# ProPrj_MPU6500__2025-10-02.net
KiCad netlist of a schematic drawn in EasyEDA Pro
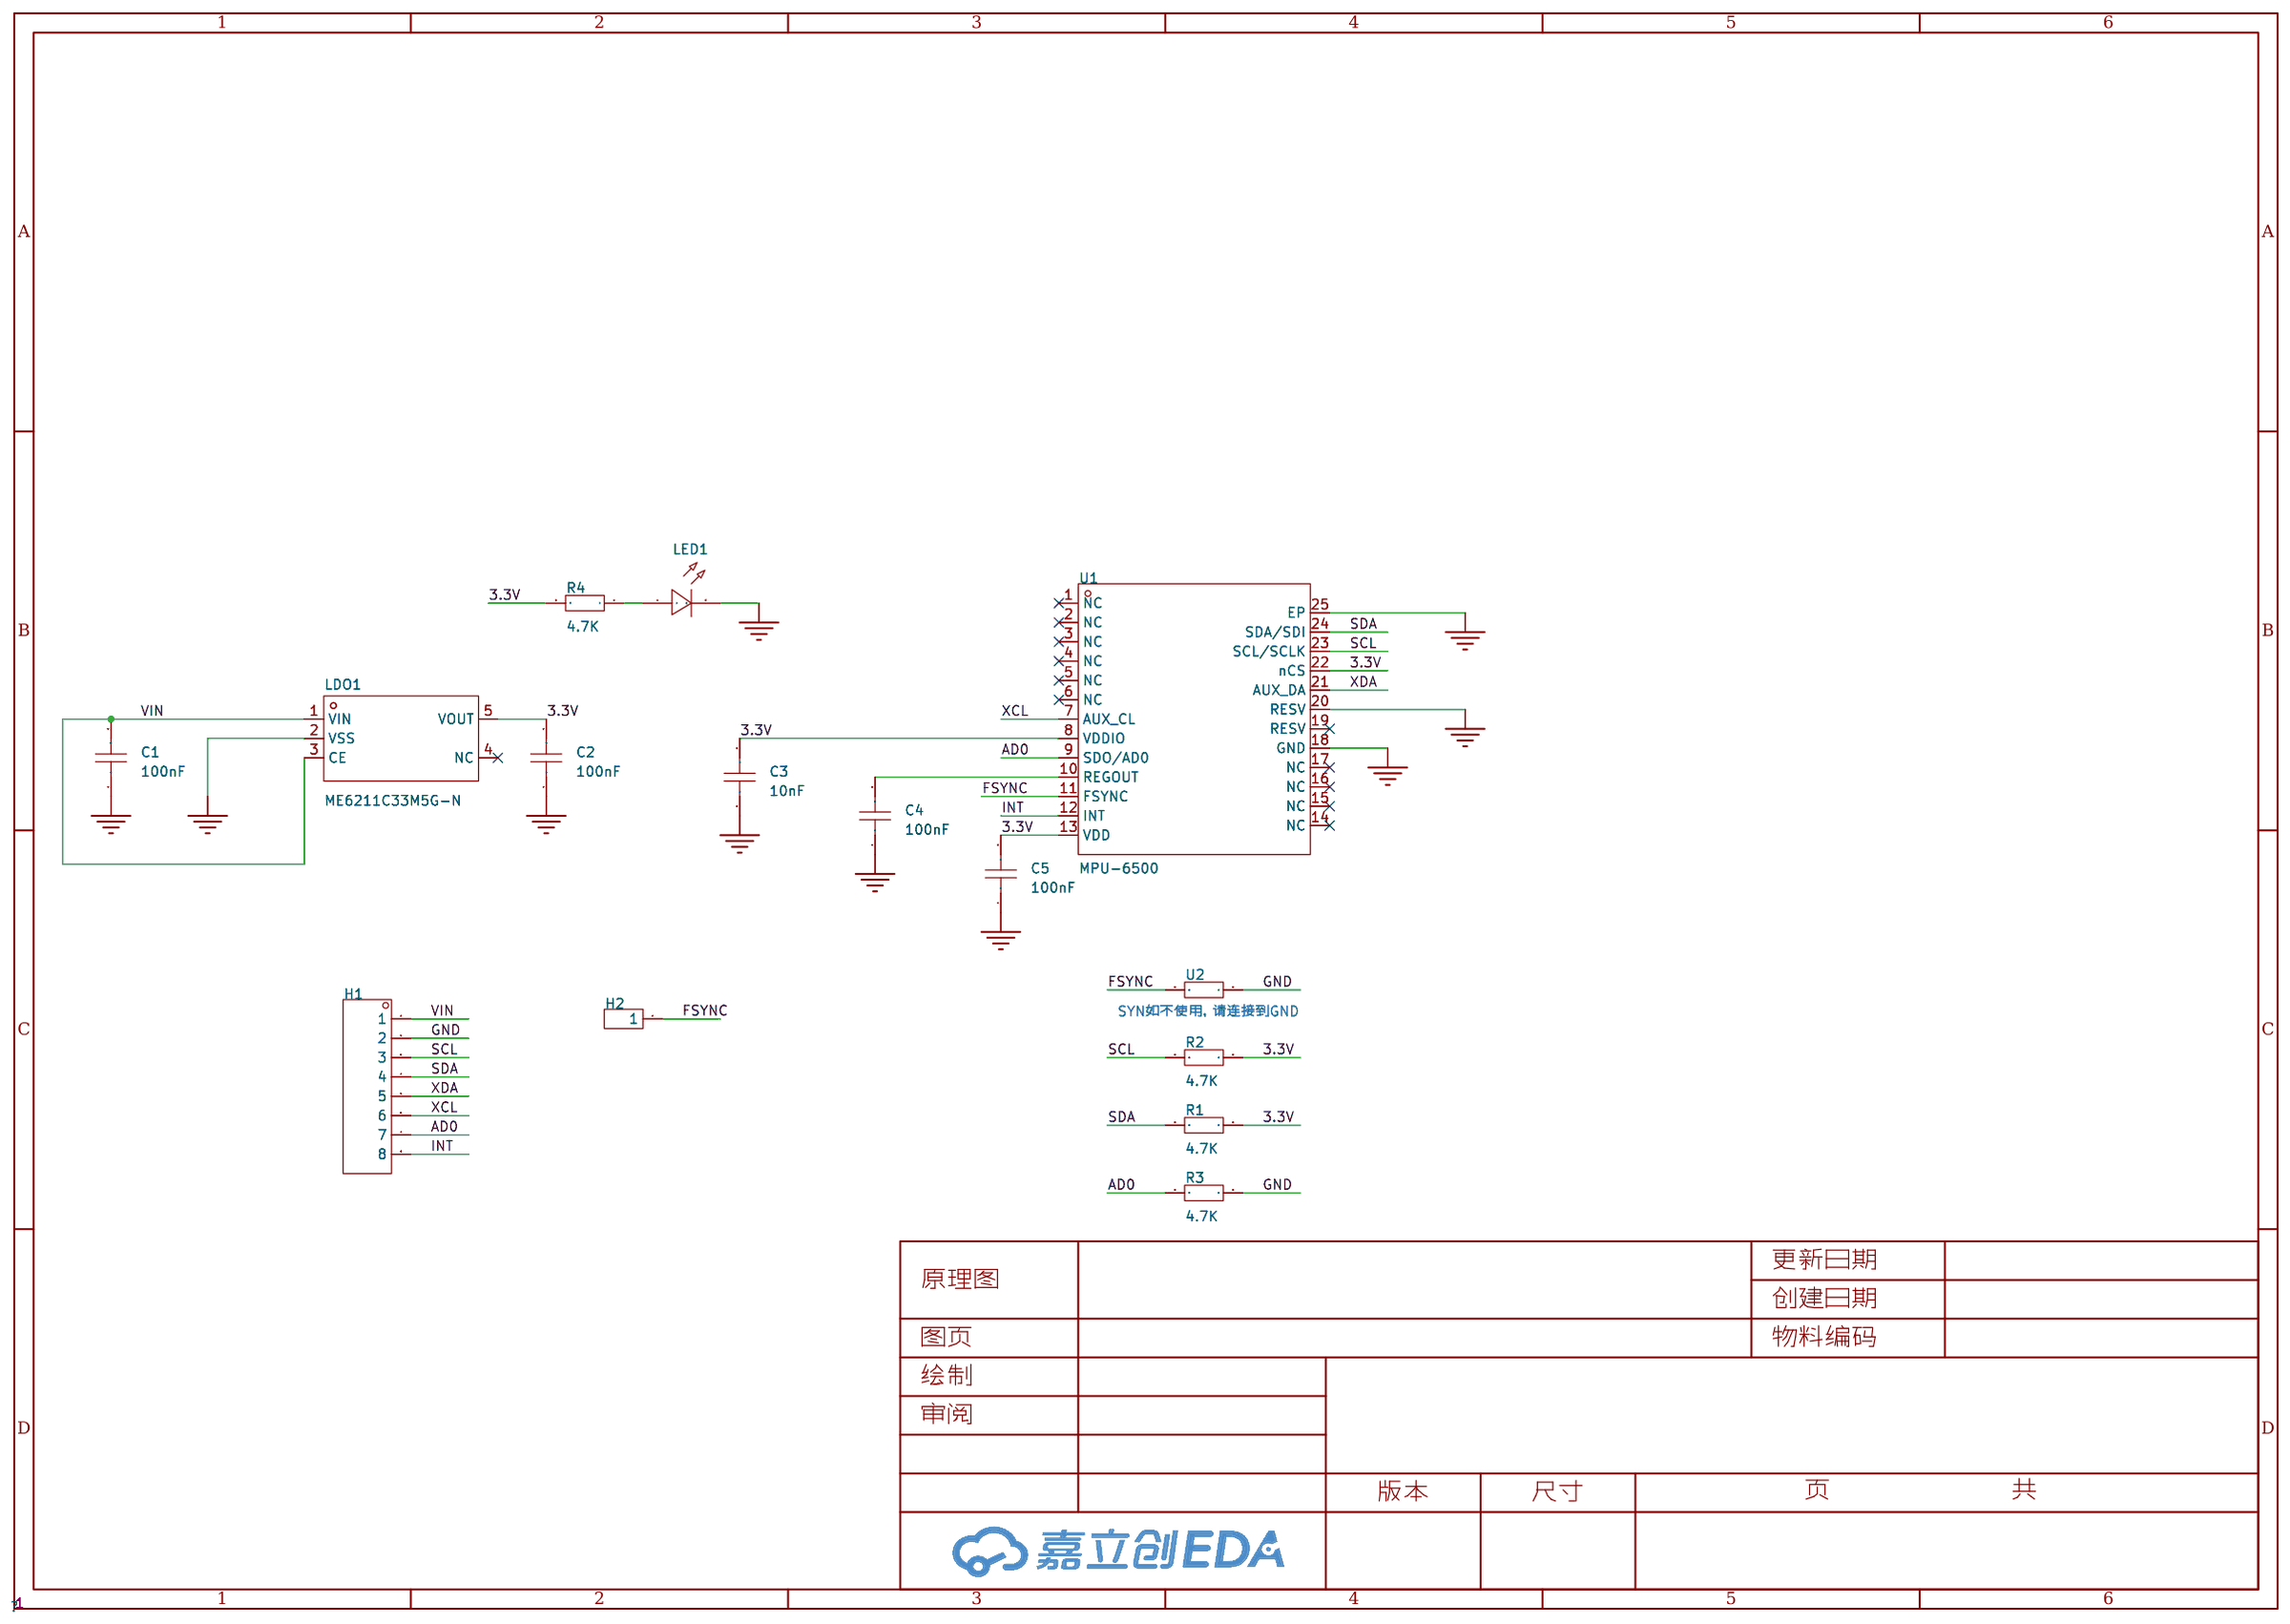
[diagram p0: schematic sheet]

(export (version "E")
  (design (tool "Eeschema 10.0.6"))
  (components
    (comp (ref "C1")
      (value "100nF")
      (footprint "easyedapro:C0603")
      (libsource (lib "easyedapro") (part "CapAcitance"))
    )
    (comp (ref "C2")
      (value "100nF")
      (footprint "easyedapro:C0603")
      (libsource (lib "easyedapro") (part "CapAcitance"))
    )
    (comp (ref "C3")
      (value "10nF")
      (footprint "easyedapro:C0603")
      (libsource (lib "easyedapro") (part "CapAcitance"))
    )
    (comp (ref "C4")
      (value "100nF")
      (footprint "easyedapro:C0603")
      (libsource (lib "easyedapro") (part "CapAcitance"))
    )
    (comp (ref "C5")
      (value "100nF")
      (footprint "easyedapro:C0603")
      (libsource (lib "easyedapro") (part "CapAcitance"))
    )
    (comp (ref "H1")
      (value "~")
      (footprint "easyedapro:HDR-TH_8P-P2.54-V-M")
      (libsource (lib "easyedapro") (part "Header-Male-2.54_1x8"))
    )
    (comp (ref "H2")
      (value "~")
      (footprint "easyedapro:HDR-TH_1P-V-M_XKB_X4611WV-01I-C28D40")
      (libsource (lib "easyedapro") (part "HDR_1x1"))
    )
    (comp (ref "LDO1")
      (value "ME6211C33M5G-N")
      (footprint "easyedapro:SOT-23-5_L3.0-W1.7-P0.95-LS2.8-BL")
      (description "输出类型:固定;最大输入电压:6V;输出电压:3.3V;最大输出电流:500mA;电源纹波抑制比(PSRR):70dB;输出极性:正极;")
      (fields (field (name "Manufacturer") "MICRONE(南京微盟)"))
      (libsource (lib "easyedapro") (part "ME6211C33M5G-N"))
    )
    (comp (ref "LED1")
      (value "~")
      (footprint "easyedapro:LED_0603_RED")
      (libsource (lib "easyedapro") (part "LED0603_R"))
    )
    (comp (ref "R1") (value "4.7K") (footprint "easyedapro:R0603") (libsource (lib "easyedapro") (part "电阻")))
    (comp (ref "R2") (value "4.7K") (footprint "easyedapro:R0603") (libsource (lib "easyedapro") (part "电阻")))
    (comp (ref "R3") (value "4.7K") (footprint "easyedapro:R0603") (libsource (lib "easyedapro") (part "电阻")))
    (comp (ref "R4") (value "4.7K") (footprint "easyedapro:R0603") (libsource (lib "easyedapro") (part "电阻")))
    (comp (ref "U1")
      (value "MPU-6500")
      (footprint "easyedapro:QFN-24_L3.0-W3.0-P0.40-BL-EP")
      (description "传感器类型:加速度计陀螺仪;")
      (fields (field (name "Manufacturer") "TDK InvenSense(应美盛)"))
      (libsource (lib "easyedapro") (part "MPU6500"))
    )
    (comp (ref "U2")
      (value "~")
      (footprint "easyedapro:R0603")
      (description "0603封装的跳线")
      (fields
        (field (name "Manufacturer Part") "0603WAF2200T5E")
        (field (name "Manufacturer") "UNI-ROYAL(厚声)")
      )
      (libsource (lib "easyedapro") (part "0603"))
    )
  )
  (nets
    (net (code "1") (name "/3.3V") (class "Default")
      (node (ref "C2") (pin "2") (pinfunction "2_2") (pintype "input"))
      (node (ref "C3") (pin "2") (pinfunction "2_2") (pintype "input"))
      (node (ref "C5") (pin "2") (pinfunction "2_2") (pintype "input"))
      (node (ref "LDO1") (pin "5") (pinfunction "VOUT_5") (pintype "input"))
      (node (ref "R1") (pin "1") (pinfunction "1_1") (pintype "input"))
      (node (ref "R2") (pin "1") (pinfunction "1_1") (pintype "input"))
      (node (ref "R4") (pin "2") (pinfunction "2_2") (pintype "input"))
      (node (ref "U1") (pin "13") (pinfunction "VDD_13") (pintype "unspecified"))
      (node (ref "U1") (pin "22") (pinfunction "nCS_22") (pintype "unspecified"))
      (node (ref "U1") (pin "8") (pinfunction "VDDIO_8") (pintype "unspecified"))
    )
    (net (code "2") (name "/AD0") (class "Default")
      (node (ref "H1") (pin "7") (pinfunction "7_7") (pintype "unspecified"))
      (node (ref "R3") (pin "2") (pinfunction "2_2") (pintype "input"))
      (node (ref "U1") (pin "9") (pinfunction "SDO/AD0_9") (pintype "unspecified"))
    )
    (net (code "3") (name "/FSYNC") (class "Default")
      (node (ref "H2") (pin "1") (pinfunction "1_1") (pintype "unspecified"))
      (node (ref "U1") (pin "11") (pinfunction "FSYNC_11") (pintype "unspecified"))
      (node (ref "U2") (pin "2") (pinfunction "2_2") (pintype "input"))
    )
    (net (code "4") (name "/INT") (class "Default")
      (node (ref "H1") (pin "8") (pinfunction "8_8") (pintype "unspecified"))
      (node (ref "U1") (pin "12") (pinfunction "INT_12") (pintype "unspecified"))
    )
    (net (code "5") (name "/SCL") (class "Default")
      (node (ref "H1") (pin "3") (pinfunction "3_3") (pintype "unspecified"))
      (node (ref "R2") (pin "2") (pinfunction "2_2") (pintype "input"))
      (node (ref "U1") (pin "23") (pinfunction "SCL/SCLK_23") (pintype "unspecified"))
    )
    (net (code "6") (name "/SDA") (class "Default")
      (node (ref "H1") (pin "4") (pinfunction "4_4") (pintype "unspecified"))
      (node (ref "R1") (pin "2") (pinfunction "2_2") (pintype "input"))
      (node (ref "U1") (pin "24") (pinfunction "SDA/SDI_24") (pintype "unspecified"))
    )
    (net (code "7") (name "/VIN") (class "Default")
      (node (ref "C1") (pin "2") (pinfunction "2_2") (pintype "input"))
      (node (ref "H1") (pin "1") (pinfunction "1_1") (pintype "unspecified"))
      (node (ref "LDO1") (pin "1") (pinfunction "VIN_1") (pintype "input"))
      (node (ref "LDO1") (pin "3") (pinfunction "CE_3") (pintype "input"))
    )
    (net (code "8") (name "/XCL") (class "Default")
      (node (ref "H1") (pin "6") (pinfunction "6_6") (pintype "unspecified"))
      (node (ref "U1") (pin "7") (pinfunction "AUX_CL_7") (pintype "unspecified"))
    )
    (net (code "9") (name "/XDA") (class "Default")
      (node (ref "H1") (pin "5") (pinfunction "5_5") (pintype "unspecified"))
      (node (ref "U1") (pin "21") (pinfunction "AUX_DA_21") (pintype "unspecified"))
    )
    (net (code "10") (name "GND") (class "Default")
      (node (ref "C1") (pin "1") (pinfunction "1_1") (pintype "input"))
      (node (ref "C2") (pin "1") (pinfunction "1_1") (pintype "input"))
      (node (ref "C3") (pin "1") (pinfunction "1_1") (pintype "input"))
      (node (ref "C4") (pin "1") (pinfunction "1_1") (pintype "input"))
      (node (ref "C5") (pin "1") (pinfunction "1_1") (pintype "input"))
      (node (ref "H1") (pin "2") (pinfunction "2_2") (pintype "unspecified"))
      (node (ref "LDO1") (pin "2") (pinfunction "VSS_2") (pintype "input"))
      (node (ref "LED1") (pin "2") (pinfunction "C_2") (pintype "input"))
      (node (ref "R3") (pin "1") (pinfunction "1_1") (pintype "input"))
      (node (ref "U1") (pin "18") (pinfunction "GND_18") (pintype "unspecified"))
      (node (ref "U1") (pin "20") (pinfunction "RESV_20") (pintype "unspecified"))
      (node (ref "U1") (pin "25") (pinfunction "EP_25") (pintype "unspecified"))
      (node (ref "U2") (pin "1") (pinfunction "1_1") (pintype "input"))
    )
    (net (code "11") (name "Net-(LED1-A)") (class "Default")
      (node (ref "LED1") (pin "1") (pinfunction "A_1") (pintype "input"))
      (node (ref "R4") (pin "1") (pinfunction "1_1") (pintype "input"))
    )
    (net (code "12") (name "Net-(U1-REGOUT)") (class "Default")
      (node (ref "C4") (pin "2") (pinfunction "2_2") (pintype "input"))
      (node (ref "U1") (pin "10") (pinfunction "REGOUT_10") (pintype "unspecified"))
    )
    (net (code "13") (name "unconnected-(LDO1-NC-Pad4)") (class "Default")
      (node (ref "LDO1") (pin "4") (pinfunction "NC_4") (pintype "input+no_connect"))
    )
    (net (code "14") (name "unconnected-(U1-NC-Pad1)") (class "Default")
      (node (ref "U1") (pin "1") (pinfunction "NC_1") (pintype "unspecified+no_connect"))
    )
    (net (code "15") (name "unconnected-(U1-NC-Pad2)") (class "Default")
      (node (ref "U1") (pin "2") (pinfunction "NC_2") (pintype "unspecified+no_connect"))
    )
    (net (code "16") (name "unconnected-(U1-NC-Pad3)") (class "Default")
      (node (ref "U1") (pin "3") (pinfunction "NC_3") (pintype "unspecified+no_connect"))
    )
    (net (code "17") (name "unconnected-(U1-NC-Pad4)") (class "Default")
      (node (ref "U1") (pin "4") (pinfunction "NC_4") (pintype "unspecified+no_connect"))
    )
    (net (code "18") (name "unconnected-(U1-NC-Pad5)") (class "Default")
      (node (ref "U1") (pin "5") (pinfunction "NC_5") (pintype "unspecified+no_connect"))
    )
    (net (code "19") (name "unconnected-(U1-NC-Pad6)") (class "Default")
      (node (ref "U1") (pin "6") (pinfunction "NC_6") (pintype "unspecified+no_connect"))
    )
    (net (code "20") (name "unconnected-(U1-NC-Pad14)") (class "Default")
      (node (ref "U1") (pin "14") (pinfunction "NC_14") (pintype "unspecified+no_connect"))
    )
    (net (code "21") (name "unconnected-(U1-NC-Pad15)") (class "Default")
      (node (ref "U1") (pin "15") (pinfunction "NC_15") (pintype "unspecified+no_connect"))
    )
    (net (code "22") (name "unconnected-(U1-NC-Pad16)") (class "Default")
      (node (ref "U1") (pin "16") (pinfunction "NC_16") (pintype "unspecified+no_connect"))
    )
    (net (code "23") (name "unconnected-(U1-NC-Pad17)") (class "Default")
      (node (ref "U1") (pin "17") (pinfunction "NC_17") (pintype "unspecified+no_connect"))
    )
    (net (code "24") (name "unconnected-(U1-RESV-Pad19)") (class "Default")
      (node (ref "U1") (pin "19") (pinfunction "RESV_19") (pintype "unspecified+no_connect"))
    )
  )
)
